# MCU.net
KiCad netlist of a schematic drawn in Altium Designer
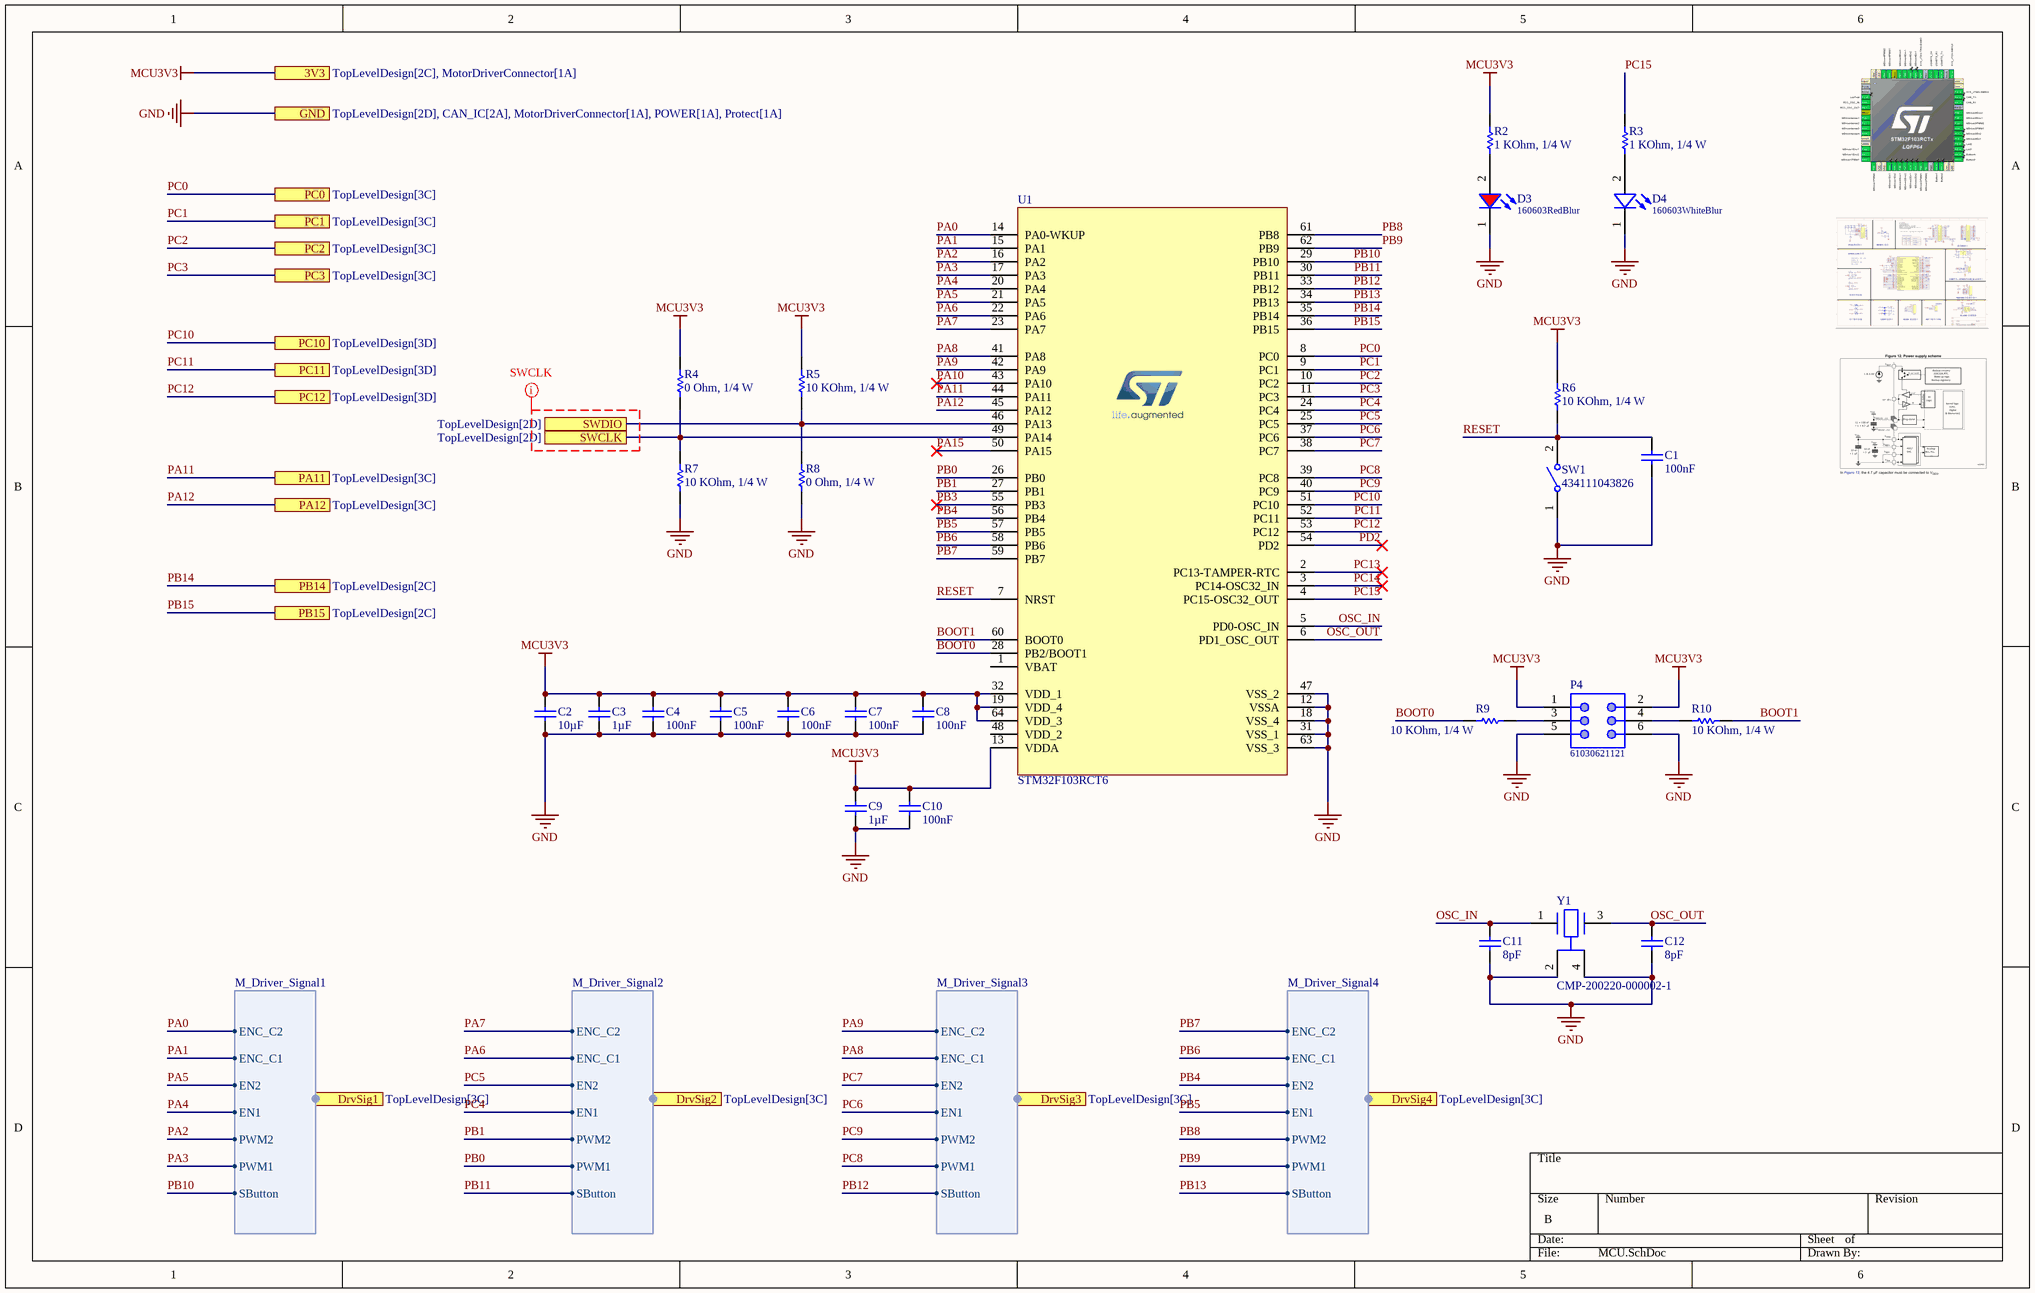
[diagram p0: MCU.SchDoc]

(export (version "E")
  (design (tool "Eeschema 10.0.6"))
  (components
    (comp (ref "C1")
      (value "100nF")
      (footprint "CAP_0603")
      (description "CAP, size 0603, 100 nF, 50 VDC")
      (fields
        (field (name "TOLERANCE") "10%")
        (field (name "Comment") "0106031041050")
        (field (name "SOURCE") "Capacitor_0603_10_percent.SchLib")
      )
      (libsource (lib "Tin Tran") (part "010603475106.3"))
    )
    (comp (ref "C2")
      (value "10µF")
      (footprint "CAP_0603")
      (description "CAP, size 0603, 10 uF, 10 VDC")
      (fields
        (field (name "TOLERANCE") "10%")
        (field (name "Comment") "0106031061010")
        (field (name "SOURCE") "Capacitor_0603_10_percent.SchLib")
      )
      (libsource (lib "Tin Tran") (part "010603475106.3"))
    )
    (comp (ref "C3")
      (value "1µF")
      (footprint "CAP_0603")
      (description "CAP, size 0603, 1 uF, 16 VDC")
      (fields
        (field (name "TOLERANCE") "10%")
        (field (name "Comment") "0106031051016")
        (field (name "SOURCE") "Capacitor_0603_10_percent.SchLib")
      )
      (libsource (lib "Tin Tran") (part "010603475106.3"))
    )
    (comp (ref "C4")
      (value "100nF")
      (footprint "CAP_0603")
      (description "CAP, size 0603, 100 nF, 50 VDC")
      (fields
        (field (name "TOLERANCE") "10%")
        (field (name "Comment") "0106031041050")
        (field (name "SOURCE") "Capacitor_0603_10_percent.SchLib")
      )
      (libsource (lib "Tin Tran") (part "010603475106.3"))
    )
    (comp (ref "C5")
      (value "100nF")
      (footprint "CAP_0603")
      (description "CAP, size 0603, 100 nF, 50 VDC")
      (fields
        (field (name "TOLERANCE") "10%")
        (field (name "Comment") "0106031041050")
        (field (name "SOURCE") "Capacitor_0603_10_percent.SchLib")
      )
      (libsource (lib "Tin Tran") (part "010603475106.3"))
    )
    (comp (ref "C6")
      (value "100nF")
      (footprint "CAP_0603")
      (description "CAP, size 0603, 100 nF, 50 VDC")
      (fields
        (field (name "TOLERANCE") "10%")
        (field (name "Comment") "0106031041050")
        (field (name "SOURCE") "Capacitor_0603_10_percent.SchLib")
      )
      (libsource (lib "Tin Tran") (part "010603475106.3"))
    )
    (comp (ref "C7")
      (value "100nF")
      (footprint "CAP_0603")
      (description "CAP, size 0603, 100 nF, 50 VDC")
      (fields
        (field (name "TOLERANCE") "10%")
        (field (name "Comment") "0106031041050")
        (field (name "SOURCE") "Capacitor_0603_10_percent.SchLib")
      )
      (libsource (lib "Tin Tran") (part "010603475106.3"))
    )
    (comp (ref "C8")
      (value "100nF")
      (footprint "CAP_0603")
      (description "CAP, size 0603, 100 nF, 50 VDC")
      (fields
        (field (name "TOLERANCE") "10%")
        (field (name "Comment") "0106031041050")
        (field (name "SOURCE") "Capacitor_0603_10_percent.SchLib")
      )
      (libsource (lib "Tin Tran") (part "010603475106.3"))
    )
    (comp (ref "C9")
      (value "1µF")
      (footprint "CAP_0603")
      (description "CAP, size 0603, 1 uF, 16 VDC")
      (fields
        (field (name "TOLERANCE") "10%")
        (field (name "Comment") "0106031051016")
        (field (name "SOURCE") "Capacitor_0603_10_percent.SchLib")
      )
      (libsource (lib "Tin Tran") (part "010603475106.3"))
    )
    (comp (ref "C10")
      (value "100nF")
      (footprint "CAP_0603")
      (description "CAP, size 0603, 100 nF, 50 VDC")
      (fields
        (field (name "TOLERANCE") "10%")
        (field (name "Comment") "0106031041050")
        (field (name "SOURCE") "Capacitor_0603_10_percent.SchLib")
      )
      (libsource (lib "Tin Tran") (part "010603475106.3"))
    )
    (comp (ref "C11")
      (value "8pF")
      (footprint "CAP_0603")
      (description "CAP, size 0603, 8 pF, 50 VDC")
      (fields
        (field (name "TOLERANCE") "5%")
        (field (name "Comment") "0106030800550")
        (field (name "SOURCE") "Capacitor_0603_5_percent.SchLib")
      )
      (libsource (lib "Tin Tran") (part "0106036820550"))
    )
    (comp (ref "C12")
      (value "8pF")
      (footprint "CAP_0603")
      (description "CAP, size 0603, 8 pF, 50 VDC")
      (fields
        (field (name "TOLERANCE") "5%")
        (field (name "Comment") "0106030800550")
        (field (name "SOURCE") "Capacitor_0603_5_percent.SchLib")
      )
      (libsource (lib "Tin Tran") (part "0106036820550"))
    )
    (comp (ref "D3")
      (value "160603RedBlur")
      (footprint "WL-SMCW_0603_H=0.7mm")
      (description "WL-SMCW SMT Mono-color Chip LED Blur, size 0603, Red, 2V, 140deg")
      (libsource (lib "Tin Tran") (part "160603RedClear"))
    )
    (comp (ref "D4")
      (value "160603WhiteBlur")
      (footprint "WL-SMCW_0603_H=0.7mm")
      (description "WL-SMCW SMT Mono-color Chip LED Blur, size 0603, White")
      (libsource (lib "Tin Tran") (part "160603WhiteClear"))
    )
    (comp (ref "P4")
      (value "61030621121")
      (footprint "61030621121")
      (description "WR-PHD Pin Header, SMT, pitch 2.54mm, Dual Row, Vertical, 6p")
      (fields (field (name "MANUFACTURER") "Wurth Elektronik"))
      (libsource (lib "Tin Tran") (part "61300621121"))
    )
    (comp (ref "R2")
      (value "1 KOhm, 1/4 W")
      (footprint "resistor_0603")
      (description "RES, size 0603, 1 KOhm, 1/4 W")
      (fields (field (name "Comment") "0006031021"))
      (libsource (lib "Tin Tran") (part "00060371541"))
    )
    (comp (ref "R3")
      (value "1 KOhm, 1/4 W")
      (footprint "resistor_0603")
      (description "RES, size 0603, 1 KOhm, 1/4 W")
      (fields (field (name "Comment") "0006031021"))
      (libsource (lib "Tin Tran") (part "00060371541"))
    )
    (comp (ref "R4")
      (value "0 Ohm, 1/4 W")
      (footprint "resistor_0603")
      (description "RES, size 0603, 0 Ohm, 1/4 W")
      (fields (field (name "Comment") "0006030001"))
      (libsource (lib "Tin Tran") (part "00060371541"))
    )
    (comp (ref "R5")
      (value "10 KOhm, 1/4 W")
      (footprint "resistor_0603")
      (description "RES, size 0603, 10 KOhm, 1/4 W")
      (fields (field (name "Comment") "0006031031"))
      (libsource (lib "Tin Tran") (part "00060371541"))
    )
    (comp (ref "R6")
      (value "10 KOhm, 1/4 W")
      (footprint "resistor_0603")
      (description "RES, size 0603, 10 KOhm, 1/4 W")
      (fields (field (name "Comment") "0006031031"))
      (libsource (lib "Tin Tran") (part "00060371541"))
    )
    (comp (ref "R7")
      (value "10 KOhm, 1/4 W")
      (footprint "resistor_0603")
      (description "RES, size 0603, 10 KOhm, 1/4 W")
      (fields (field (name "Comment") "0006031031"))
      (libsource (lib "Tin Tran") (part "00060371541"))
    )
    (comp (ref "R8")
      (value "0 Ohm, 1/4 W")
      (footprint "resistor_0603")
      (description "RES, size 0603, 0 Ohm, 1/4 W")
      (fields (field (name "Comment") "0006030001"))
      (libsource (lib "Tin Tran") (part "00060371541"))
    )
    (comp (ref "R9")
      (value "10 KOhm, 1/4 W")
      (footprint "resistor_0603")
      (description "RES, size 0603, 10 KOhm, 1/4 W")
      (fields (field (name "Comment") "0006031031"))
      (libsource (lib "Tin Tran") (part "00060371541"))
    )
    (comp (ref "R10")
      (value "10 KOhm, 1/4 W")
      (footprint "resistor_0603")
      (description "RES, size 0603, 10 KOhm, 1/4 W")
      (fields (field (name "Comment") "0006031031"))
      (libsource (lib "Tin Tran") (part "00060371541"))
    )
    (comp (ref "SW1")
      (value "434111043826")
      (footprint "WS-TASV_L6W3.5H4.3_4341x10438x6")
      (description "WS-TASV SMT Tact Switch, L6 x W3.5 x H4.3mm, 260g, SPST-NO, 12V, 50mA")
      (fields (field (name "MANUFACTURER") "Wurth Elektronik"))
      (libsource (lib "Tin Tran") (part "434111050826"))
    )
    (comp (ref "U1")
      (value "STM32F103RCT6")
      (footprint "QFP50P1200X1200X160-64N")
      (description "ARMÂ® CortexÂ®-M3 STM32F1 Microcontroller IC 32-Bit 72MHz 256KB (256K x 8) FLASH 64-LQFP (10x10)")
      (fields (field (name "MF") "STMicroelectronics"))
      (libsource (lib "Tin Tran") (part "STM32F103RCT6"))
    )
    (comp (ref "Y1")
      (value "CMP-200220-000002-1")
      (footprint "FP-NX3225SA-MFG")
      (description "CRYSTAL 8.000MHZ 8PF SMD")
      (fields
        (field (name "OCTOPART") "https://octopart.com/nx3225sa-25.000m-std-crs-2-ndk-51374293")
        (field (name "TOLERANCE") "15ppm")
      )
      (libsource (lib "Tin Tran") (part "CMP-200220-000002-1"))
    )
  )
  (nets
    (net (code "5") (name "/BOOT0") (class "Default")
      (node (ref "R9") (pin "1") (pinfunction "1_1") (pintype "passive"))
      (node (ref "U1") (pin "28") (pinfunction "PB2/BOOT1_28") (pintype "passive"))
    )
    (net (code "6") (name "/BOOT1") (class "Default")
      (node (ref "R10") (pin "1") (pinfunction "1_1") (pintype "passive"))
      (node (ref "U1") (pin "60") (pinfunction "BOOT0_60") (pintype "passive"))
    )
    (net (code "7") (name "/OSC_IN") (class "Default")
      (node (ref "C11") (pin "2") (pinfunction "2_2") (pintype "passive"))
      (node (ref "U1") (pin "5") (pinfunction "PD0-OSC_IN_5") (pintype "passive"))
      (node (ref "Y1") (pin "1") (pinfunction "1_1") (pintype "passive"))
    )
    (net (code "8") (name "/OSC_OUT") (class "Default")
      (node (ref "C12") (pin "2") (pinfunction "2_2") (pintype "passive"))
      (node (ref "U1") (pin "6") (pinfunction "PD1_OSC_OUT_6") (pintype "passive"))
      (node (ref "Y1") (pin "3") (pinfunction "3_3") (pintype "passive"))
    )
    (net (code "9") (name "/PA0") (class "Default")
      (node (ref "U1") (pin "14") (pinfunction "PA0-WKUP_14") (pintype "passive"))
    )
    (net (code "10") (name "/PA1") (class "Default")
      (node (ref "U1") (pin "15") (pinfunction "PA1_15") (pintype "passive"))
    )
    (net (code "11") (name "/PA2") (class "Default")
      (node (ref "U1") (pin "16") (pinfunction "PA2_16") (pintype "passive"))
    )
    (net (code "12") (name "/PA3") (class "Default")
      (node (ref "U1") (pin "17") (pinfunction "PA3_17") (pintype "passive"))
    )
    (net (code "13") (name "/PA4") (class "Default")
      (node (ref "U1") (pin "20") (pinfunction "PA4_20") (pintype "passive"))
    )
    (net (code "14") (name "/PA5") (class "Default")
      (node (ref "U1") (pin "21") (pinfunction "PA5_21") (pintype "passive"))
    )
    (net (code "15") (name "/PA6") (class "Default")
      (node (ref "U1") (pin "22") (pinfunction "PA6_22") (pintype "passive"))
    )
    (net (code "16") (name "/PA7") (class "Default")
      (node (ref "U1") (pin "23") (pinfunction "PA7_23") (pintype "passive"))
    )
    (net (code "17") (name "/PA8") (class "Default")
      (node (ref "U1") (pin "41") (pinfunction "PA8_41") (pintype "passive"))
    )
    (net (code "18") (name "/PA9") (class "Default")
      (node (ref "U1") (pin "42") (pinfunction "PA9_42") (pintype "passive"))
    )
    (net (code "19") (name "/PA10") (class "Default")
      (node (ref "U1") (pin "43") (pinfunction "PA10_43") (pintype "passive+no_connect"))
    )
    (net (code "20") (name "/PA11") (class "Default")
      (node (ref "U1") (pin "44") (pinfunction "PA11_44") (pintype "passive"))
    )
    (net (code "21") (name "/PA12") (class "Default")
      (node (ref "U1") (pin "45") (pinfunction "PA12_45") (pintype "passive"))
    )
    (net (code "22") (name "/PA15") (class "Default")
      (node (ref "U1") (pin "50") (pinfunction "PA15_50") (pintype "passive+no_connect"))
    )
    (net (code "23") (name "/PB0") (class "Default")
      (node (ref "U1") (pin "26") (pinfunction "PB0_26") (pintype "passive"))
    )
    (net (code "24") (name "/PB1") (class "Default")
      (node (ref "U1") (pin "27") (pinfunction "PB1_27") (pintype "passive"))
    )
    (net (code "25") (name "/PB3") (class "Default")
      (node (ref "U1") (pin "55") (pinfunction "PB3_55") (pintype "passive+no_connect"))
    )
    (net (code "26") (name "/PB4") (class "Default")
      (node (ref "U1") (pin "56") (pinfunction "PB4_56") (pintype "passive"))
    )
    (net (code "27") (name "/PB5") (class "Default")
      (node (ref "U1") (pin "57") (pinfunction "PB5_57") (pintype "passive"))
    )
    (net (code "28") (name "/PB6") (class "Default")
      (node (ref "U1") (pin "58") (pinfunction "PB6_58") (pintype "passive"))
    )
    (net (code "29") (name "/PB7") (class "Default")
      (node (ref "U1") (pin "59") (pinfunction "PB7_59") (pintype "passive"))
    )
    (net (code "30") (name "/PB8") (class "Default")
      (node (ref "U1") (pin "61") (pinfunction "PB8_61") (pintype "passive"))
    )
    (net (code "31") (name "/PB9") (class "Default")
      (node (ref "U1") (pin "62") (pinfunction "PB9_62") (pintype "passive"))
    )
    (net (code "32") (name "/PB10") (class "Default")
      (node (ref "U1") (pin "29") (pinfunction "PB10_29") (pintype "passive"))
    )
    (net (code "33") (name "/PB11") (class "Default")
      (node (ref "U1") (pin "30") (pinfunction "PB11_30") (pintype "passive"))
    )
    (net (code "34") (name "/PB12") (class "Default")
      (node (ref "U1") (pin "33") (pinfunction "PB12_33") (pintype "passive"))
    )
    (net (code "35") (name "/PB13") (class "Default")
      (node (ref "U1") (pin "34") (pinfunction "PB13_34") (pintype "passive"))
    )
    (net (code "36") (name "/PB14") (class "Default")
      (node (ref "U1") (pin "35") (pinfunction "PB14_35") (pintype "passive"))
    )
    (net (code "37") (name "/PB15") (class "Default")
      (node (ref "U1") (pin "36") (pinfunction "PB15_36") (pintype "passive"))
    )
    (net (code "38") (name "/PC0") (class "Default")
      (node (ref "U1") (pin "8") (pinfunction "PC0_8") (pintype "passive"))
    )
    (net (code "39") (name "/PC1") (class "Default")
      (node (ref "U1") (pin "9") (pinfunction "PC1_9") (pintype "passive"))
    )
    (net (code "40") (name "/PC2") (class "Default")
      (node (ref "U1") (pin "10") (pinfunction "PC2_10") (pintype "passive"))
    )
    (net (code "41") (name "/PC3") (class "Default")
      (node (ref "U1") (pin "11") (pinfunction "PC3_11") (pintype "passive"))
    )
    (net (code "42") (name "/PC4") (class "Default")
      (node (ref "U1") (pin "24") (pinfunction "PC4_24") (pintype "passive"))
    )
    (net (code "43") (name "/PC5") (class "Default")
      (node (ref "U1") (pin "25") (pinfunction "PC5_25") (pintype "passive"))
    )
    (net (code "44") (name "/PC6") (class "Default")
      (node (ref "U1") (pin "37") (pinfunction "PC6_37") (pintype "passive"))
    )
    (net (code "45") (name "/PC7") (class "Default")
      (node (ref "U1") (pin "38") (pinfunction "PC7_38") (pintype "passive"))
    )
    (net (code "46") (name "/PC8") (class "Default")
      (node (ref "U1") (pin "39") (pinfunction "PC8_39") (pintype "passive"))
    )
    (net (code "47") (name "/PC9") (class "Default")
      (node (ref "U1") (pin "40") (pinfunction "PC9_40") (pintype "passive"))
    )
    (net (code "48") (name "/PC10") (class "Default")
      (node (ref "U1") (pin "51") (pinfunction "PC10_51") (pintype "passive"))
    )
    (net (code "49") (name "/PC11") (class "Default")
      (node (ref "U1") (pin "52") (pinfunction "PC11_52") (pintype "passive"))
    )
    (net (code "50") (name "/PC12") (class "Default")
      (node (ref "U1") (pin "53") (pinfunction "PC12_53") (pintype "passive"))
    )
    (net (code "51") (name "/PC13") (class "Default")
      (node (ref "U1") (pin "2") (pinfunction "PC13-TAMPER-RTC_2") (pintype "passive+no_connect"))
    )
    (net (code "52") (name "/PC14") (class "Default")
      (node (ref "U1") (pin "3") (pinfunction "PC14-OSC32_IN_3") (pintype "passive+no_connect"))
    )
    (net (code "53") (name "/PC15") (class "Default")
      (node (ref "R3") (pin "2") (pinfunction "2_2") (pintype "passive"))
      (node (ref "U1") (pin "4") (pinfunction "PC15-OSC32_OUT_4") (pintype "passive"))
    )
    (net (code "54") (name "/PD2") (class "Default")
      (node (ref "U1") (pin "54") (pinfunction "PD2_54") (pintype "passive+no_connect"))
    )
    (net (code "55") (name "/RESET") (class "Default")
      (node (ref "C1") (pin "2") (pinfunction "2_2") (pintype "passive"))
      (node (ref "R6") (pin "1") (pinfunction "1_1") (pintype "passive"))
      (node (ref "SW1") (pin "2") (pinfunction "2_2") (pintype "passive"))
      (node (ref "U1") (pin "7") (pinfunction "NRST_7") (pintype "passive"))
    )
    (net (code "56") (name "/SWCLK") (class "Default")
      (node (ref "R4") (pin "1") (pinfunction "1_1") (pintype "passive"))
      (node (ref "R7") (pin "2") (pinfunction "2_2") (pintype "passive"))
      (node (ref "U1") (pin "49") (pinfunction "PA14_49") (pintype "passive"))
    )
    (net (code "57") (name "/SWDIO") (class "Default")
      (node (ref "R5") (pin "1") (pinfunction "1_1") (pintype "passive"))
      (node (ref "R8") (pin "2") (pinfunction "2_2") (pintype "passive"))
      (node (ref "U1") (pin "46") (pinfunction "PA13_46") (pintype "passive"))
    )
    (net (code "62") (name "GND") (class "Default")
      (node (ref "C1") (pin "1") (pinfunction "1_1") (pintype "passive"))
      (node (ref "C10") (pin "1") (pinfunction "1_1") (pintype "passive"))
      (node (ref "C11") (pin "1") (pinfunction "1_1") (pintype "passive"))
      (node (ref "C12") (pin "1") (pinfunction "1_1") (pintype "passive"))
      (node (ref "C2") (pin "1") (pinfunction "1_1") (pintype "passive"))
      (node (ref "C3") (pin "1") (pinfunction "1_1") (pintype "passive"))
      (node (ref "C4") (pin "1") (pinfunction "1_1") (pintype "passive"))
      (node (ref "C5") (pin "1") (pinfunction "1_1") (pintype "passive"))
      (node (ref "C6") (pin "1") (pinfunction "1_1") (pintype "passive"))
      (node (ref "C7") (pin "1") (pinfunction "1_1") (pintype "passive"))
      (node (ref "C8") (pin "1") (pinfunction "1_1") (pintype "passive"))
      (node (ref "C9") (pin "1") (pinfunction "1_1") (pintype "passive"))
      (node (ref "D3") (pin "1") (pinfunction "K_1") (pintype "passive"))
      (node (ref "D4") (pin "1") (pinfunction "K_1") (pintype "passive"))
      (node (ref "P4") (pin "5") (pinfunction "5_5") (pintype "passive"))
      (node (ref "P4") (pin "6") (pinfunction "6_6") (pintype "passive"))
      (node (ref "R7") (pin "1") (pinfunction "1_1") (pintype "passive"))
      (node (ref "R8") (pin "1") (pinfunction "1_1") (pintype "passive"))
      (node (ref "SW1") (pin "1") (pinfunction "1_1") (pintype "passive"))
      (node (ref "U1") (pin "12") (pinfunction "VSSA_12") (pintype "power_in"))
      (node (ref "U1") (pin "18") (pinfunction "VSS_4_18") (pintype "power_in"))
      (node (ref "U1") (pin "31") (pinfunction "VSS_1_31") (pintype "power_in"))
      (node (ref "U1") (pin "47") (pinfunction "VSS_2_47") (pintype "power_in"))
      (node (ref "U1") (pin "63") (pinfunction "VSS_3_63") (pintype "power_in"))
      (node (ref "Y1") (pin "2") (pinfunction "GND_2") (pintype "power_in"))
      (node (ref "Y1") (pin "4") (pinfunction "GND_4") (pintype "power_in"))
    )
    (net (code "63") (name "MCU3V3") (class "Default")
      (node (ref "C10") (pin "2") (pinfunction "2_2") (pintype "passive"))
      (node (ref "C2") (pin "2") (pinfunction "2_2") (pintype "passive"))
      (node (ref "C3") (pin "2") (pinfunction "2_2") (pintype "passive"))
      (node (ref "C4") (pin "2") (pinfunction "2_2") (pintype "passive"))
      (node (ref "C5") (pin "2") (pinfunction "2_2") (pintype "passive"))
      (node (ref "C6") (pin "2") (pinfunction "2_2") (pintype "passive"))
      (node (ref "C7") (pin "2") (pinfunction "2_2") (pintype "passive"))
      (node (ref "C8") (pin "2") (pinfunction "2_2") (pintype "passive"))
      (node (ref "C9") (pin "2") (pinfunction "2_2") (pintype "passive"))
      (node (ref "P4") (pin "1") (pinfunction "1_1") (pintype "passive"))
      (node (ref "P4") (pin "2") (pinfunction "2_2") (pintype "passive"))
      (node (ref "R2") (pin "2") (pinfunction "2_2") (pintype "passive"))
      (node (ref "R4") (pin "2") (pinfunction "2_2") (pintype "passive"))
      (node (ref "R5") (pin "2") (pinfunction "2_2") (pintype "passive"))
      (node (ref "R6") (pin "2") (pinfunction "2_2") (pintype "passive"))
      (node (ref "U1") (pin "13") (pinfunction "VDDA_13") (pintype "passive"))
      (node (ref "U1") (pin "19") (pinfunction "VDD_4_19") (pintype "passive"))
      (node (ref "U1") (pin "32") (pinfunction "VDD_1_32") (pintype "passive"))
      (node (ref "U1") (pin "64") (pinfunction "VDD_3_64") (pintype "passive"))
    )
    (net (code "64") (name "Net-(D3-A)") (class "Default")
      (node (ref "D3") (pin "2") (pinfunction "A_2") (pintype "passive"))
      (node (ref "R2") (pin "1") (pinfunction "1_1") (pintype "passive"))
    )
    (net (code "65") (name "Net-(D4-A)") (class "Default")
      (node (ref "D4") (pin "2") (pinfunction "A_2") (pintype "passive"))
      (node (ref "R3") (pin "1") (pinfunction "1_1") (pintype "passive"))
    )
    (net (code "66") (name "Net-(P4-Pad3)") (class "Default")
      (node (ref "P4") (pin "3") (pinfunction "3_3") (pintype "passive"))
      (node (ref "R9") (pin "2") (pinfunction "2_2") (pintype "passive"))
    )
    (net (code "67") (name "Net-(P4-Pad4)") (class "Default")
      (node (ref "P4") (pin "4") (pinfunction "4_4") (pintype "passive"))
      (node (ref "R10") (pin "2") (pinfunction "2_2") (pintype "passive"))
    )
    (net (code "68") (name "unconnected-(U1-VBAT-Pad1)") (class "Default")
      (node (ref "U1") (pin "1") (pinfunction "VBAT_1") (pintype "passive"))
    )
    (net (code "69") (name "unconnected-(U1-VDD_2-Pad48)") (class "Default")
      (node (ref "U1") (pin "48") (pinfunction "VDD_2_48") (pintype "passive"))
    )
  )
)
